# Schematic.net
KiCad netlist of a schematic drawn in EAGLE
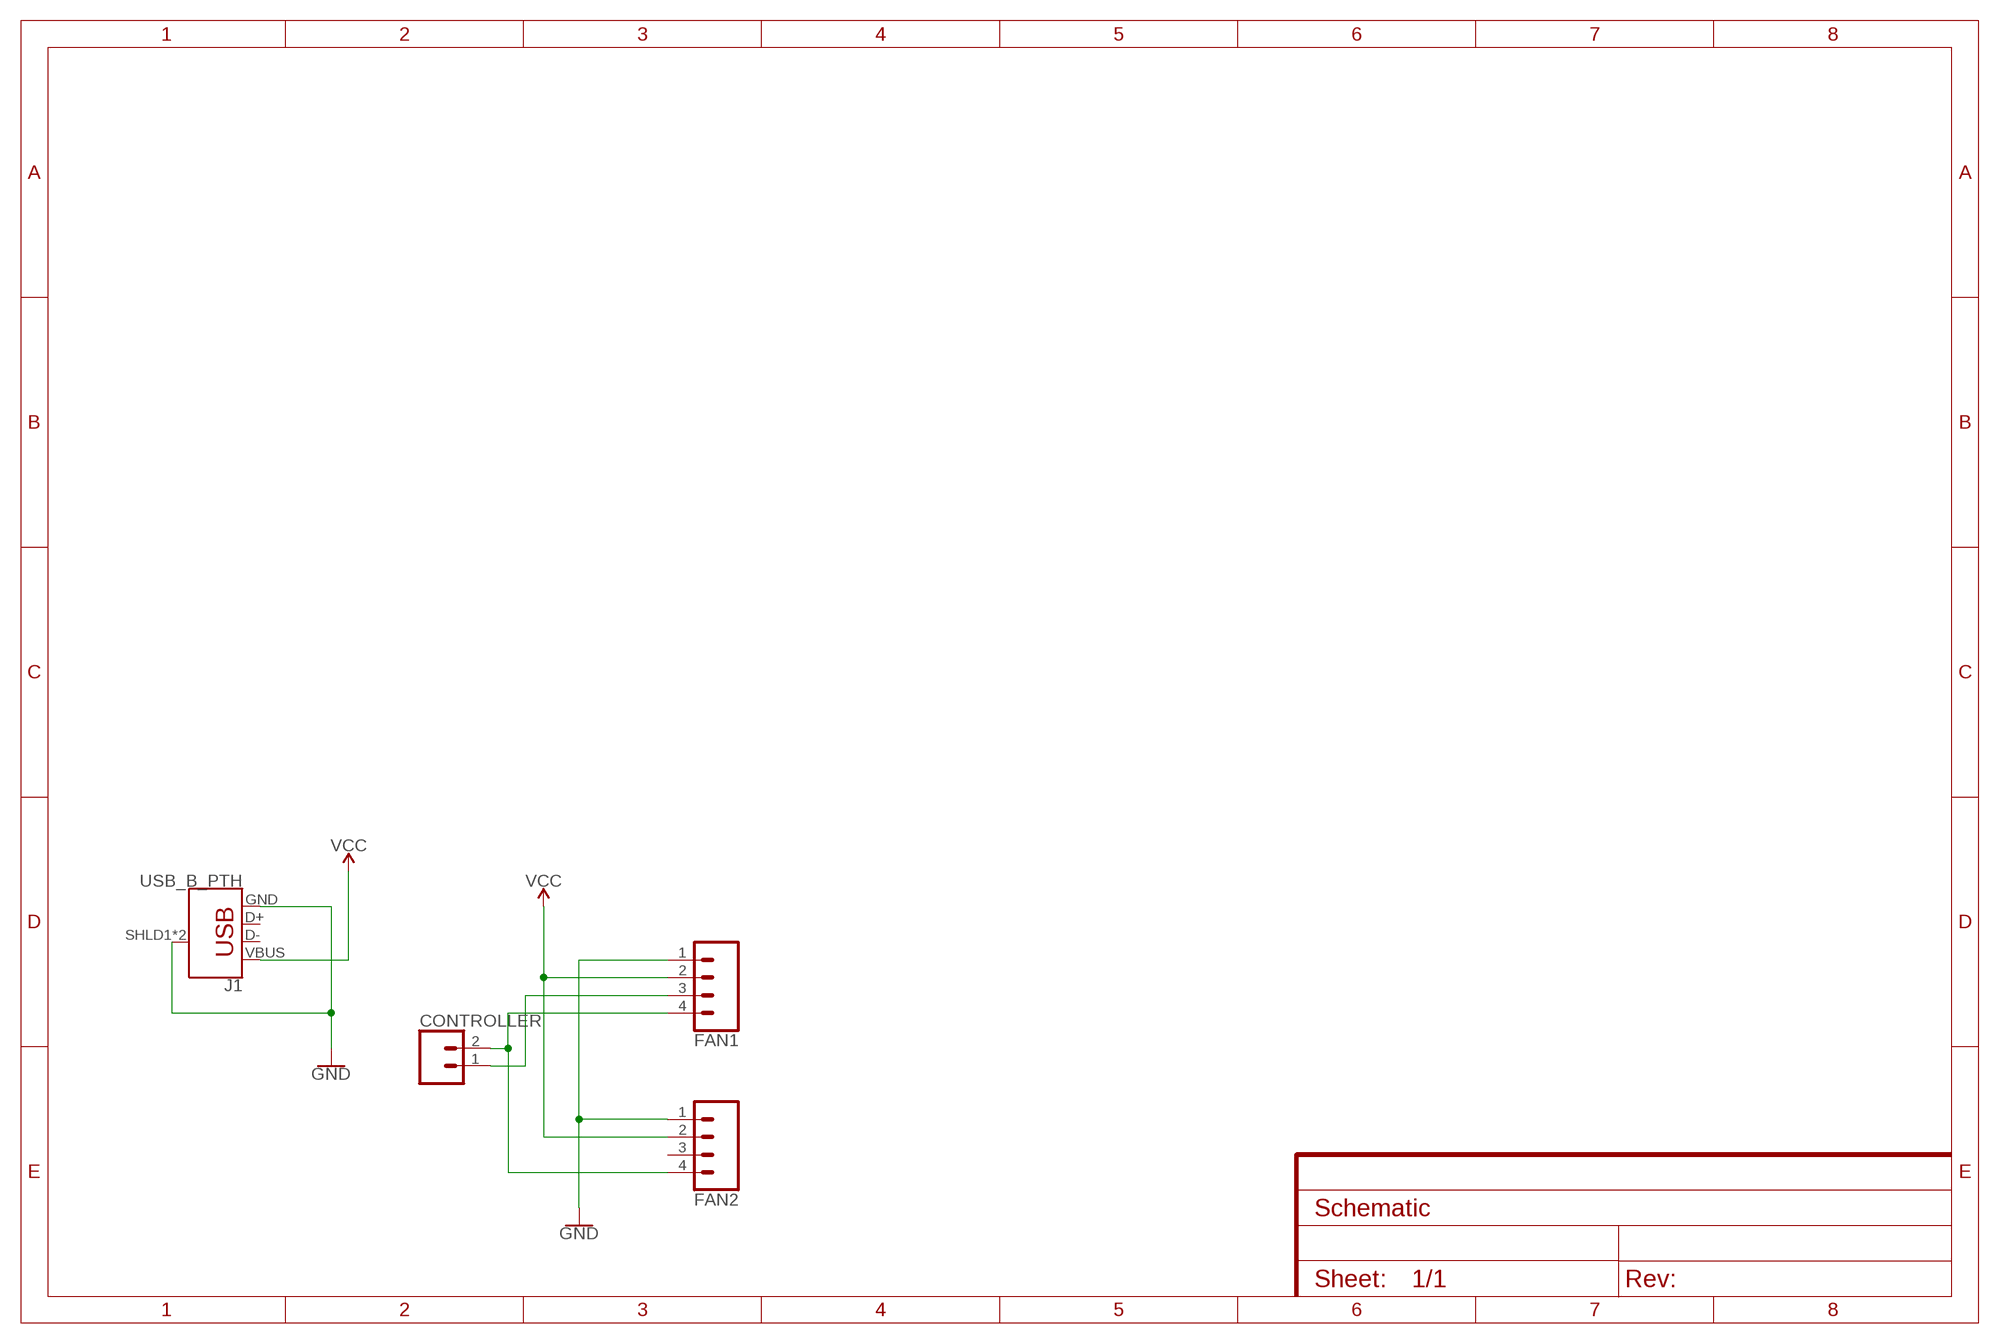
[diagram p0: schematic, sheet 1]

(export (version "E")
  (design (tool "Eeschema 10.0.6"))
  (components
    (comp (ref "CONTROLLER")
      (value "CONN_02")
      (footprint "eagle-import:1X02")
      (libsource (lib "eagle-import") (part "CONN_02"))
    )
    (comp (ref "FAN1")
      (value "CONN_04POLAR")
      (footprint "eagle-import:MOLEX-1X4")
      (libsource (lib "eagle-import") (part "CONN_04POLAR"))
    )
    (comp (ref "FAN2")
      (value "CONN_04POLAR")
      (footprint "eagle-import:MOLEX-1X4")
      (libsource (lib "eagle-import") (part "CONN_04POLAR"))
    )
    (comp (ref "J1")
      (value "USB_B_PTH")
      (footprint "eagle-import:USB-B-PTH")
      (libsource (lib "eagle-import") (part "USB_B_PTH"))
    )
  )
  (nets
    (net (code "1") (name "GND") (class "Default")
      (node (ref "FAN1") (pin "1") (pinfunction "1_1") (pintype "passive"))
      (node (ref "FAN2") (pin "1") (pinfunction "1_1") (pintype "passive"))
      (node (ref "J1") (pin "GND") (pinfunction "GND_GND") (pintype "power_in"))
      (node (ref "J1") (pin "SHLD1") (pinfunction "SHIELD_SHLD1") (pintype "bidirectional"))
      (node (ref "J1") (pin "SHLD2") (pinfunction "SHIELD_SHLD2") (pintype "bidirectional"))
    )
    (net (code "2") (name "Net-(CONTROLLER-Pad1)") (class "Default")
      (node (ref "CONTROLLER") (pin "1") (pinfunction "1_1") (pintype "passive"))
      (node (ref "FAN1") (pin "3") (pinfunction "3_3") (pintype "passive"))
    )
    (net (code "3") (name "Net-(CONTROLLER-Pad2)") (class "Default")
      (node (ref "CONTROLLER") (pin "2") (pinfunction "2_2") (pintype "passive"))
      (node (ref "FAN1") (pin "4") (pinfunction "4_4") (pintype "passive"))
      (node (ref "FAN2") (pin "4") (pinfunction "4_4") (pintype "passive"))
    )
    (net (code "4") (name "VCC") (class "Default")
      (node (ref "FAN1") (pin "2") (pinfunction "2_2") (pintype "passive"))
      (node (ref "FAN2") (pin "2") (pinfunction "2_2") (pintype "passive"))
      (node (ref "J1") (pin "VBUS") (pinfunction "VBUS_VBUS") (pintype "power_in"))
    )
    (net (code "5") (name "unconnected-(FAN2-Pad3)") (class "Default")
      (node (ref "FAN2") (pin "3") (pinfunction "3_3") (pintype "passive"))
    )
    (net (code "6") (name "unconnected-(J1-PadD+)") (class "Default")
      (node (ref "J1") (pin "D+") (pinfunction "D+_D+") (pintype "bidirectional"))
    )
    (net (code "7") (name "unconnected-(J1-PadD-)") (class "Default")
      (node (ref "J1") (pin "D-") (pinfunction "D-_D-") (pintype "bidirectional"))
    )
  )
)
